# 03-ADC.net
KiCad netlist of a schematic drawn in Altium Designer
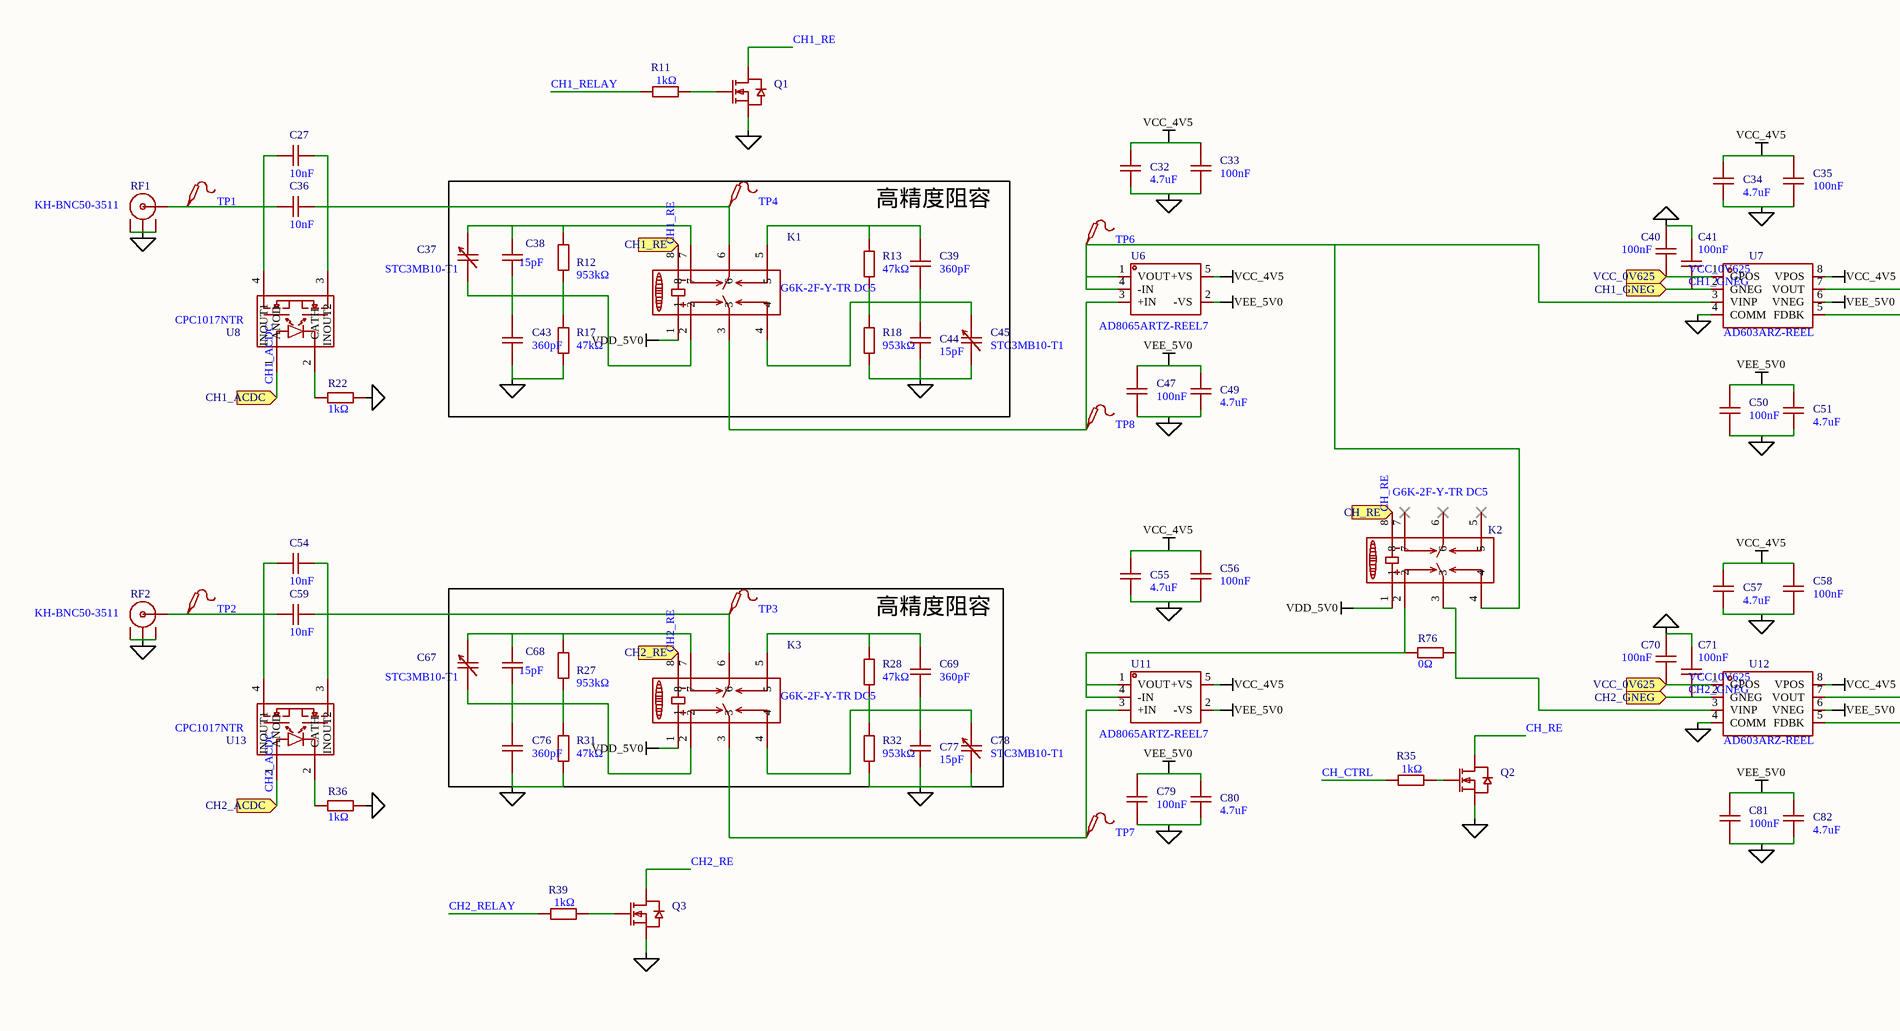
[diagram p0: 03-ADC.schdoc, left]
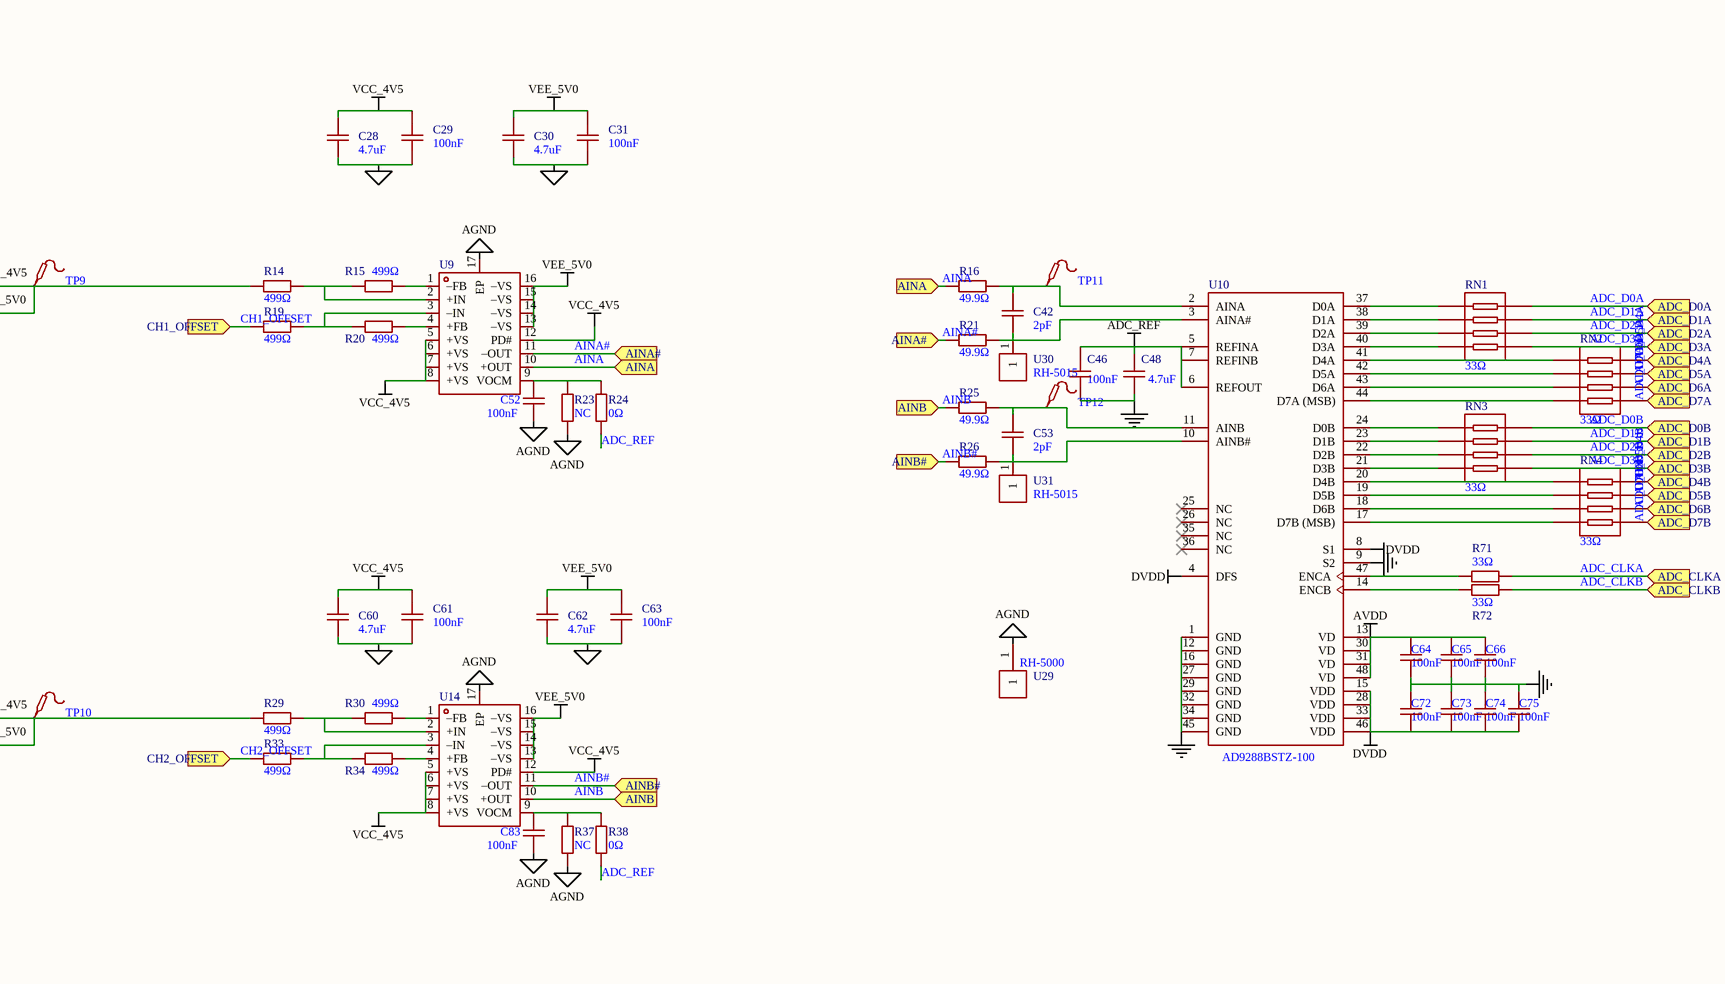
[diagram p1: 03-ADC.schdoc, right]

(export (version "E")
  (design (tool "Eeschema 10.0.6"))
  (components
    (comp (ref "C27")
      (value "10nF")
      (footprint "C0603")
      (fields
        (field (name "MANUFACTURER") "YAGEO(国巨)")
        (field (name "MANUFACTURER PART") "CC0603KRX7R9BB103")
        (field (name "TOLERANCE") "±10%")
      )
      (libsource (lib "altium-import") (part "root_0_CC0603KRX7R9BB103_"))
    )
    (comp (ref "C28")
      (value "4.7uF")
      (footprint "C0603")
      (fields
        (field (name "MANUFACTURER") "SAMSUNG(三星)")
        (field (name "MANUFACTURER PART") "CL10A475KO8NNNC")
        (field (name "TOLERANCE") "±10%")
      )
      (libsource (lib "altium-import") (part "root_1_CL10A475KO8NNNC_"))
    )
    (comp (ref "C29")
      (value "100nF")
      (footprint "C0603")
      (fields
        (field (name "MANUFACTURER") "HRE(芯声)")
        (field (name "MANUFACTURER PART") "CGA0603X7R104K500JT")
        (field (name "TOLERANCE") "±10%")
      )
      (libsource (lib "") (part "root_1_CGA0603X7R104K500JT__1"))
    )
    (comp (ref "C30")
      (value "4.7uF")
      (footprint "C0603")
      (fields
        (field (name "MANUFACTURER") "SAMSUNG(三星)")
        (field (name "MANUFACTURER PART") "CL10A475KO8NNNC")
        (field (name "TOLERANCE") "±10%")
      )
      (libsource (lib "altium-import") (part "root_1_CL10A475KO8NNNC_"))
    )
    (comp (ref "C31")
      (value "100nF")
      (footprint "C0603")
      (fields
        (field (name "MANUFACTURER") "HRE(芯声)")
        (field (name "MANUFACTURER PART") "CGA0603X7R104K500JT")
        (field (name "TOLERANCE") "±10%")
      )
      (libsource (lib "") (part "root_1_CGA0603X7R104K500JT__1"))
    )
    (comp (ref "C32")
      (value "4.7uF")
      (footprint "C0603")
      (fields
        (field (name "MANUFACTURER") "SAMSUNG(三星)")
        (field (name "MANUFACTURER PART") "CL10A475KO8NNNC")
        (field (name "TOLERANCE") "±10%")
      )
      (libsource (lib "altium-import") (part "root_1_CL10A475KO8NNNC_"))
    )
    (comp (ref "C33")
      (value "100nF")
      (footprint "C0603")
      (fields
        (field (name "MANUFACTURER") "HRE(芯声)")
        (field (name "MANUFACTURER PART") "CGA0603X7R104K500JT")
        (field (name "TOLERANCE") "±10%")
      )
      (libsource (lib "") (part "root_1_CGA0603X7R104K500JT__1"))
    )
    (comp (ref "C34")
      (value "4.7uF")
      (footprint "C0603")
      (fields
        (field (name "MANUFACTURER") "SAMSUNG(三星)")
        (field (name "MANUFACTURER PART") "CL10A475KO8NNNC")
        (field (name "TOLERANCE") "±10%")
      )
      (libsource (lib "altium-import") (part "root_1_CL10A475KO8NNNC_"))
    )
    (comp (ref "C35")
      (value "100nF")
      (footprint "C0603")
      (fields
        (field (name "MANUFACTURER") "HRE(芯声)")
        (field (name "MANUFACTURER PART") "CGA0603X7R104K500JT")
        (field (name "TOLERANCE") "±10%")
      )
      (libsource (lib "") (part "root_1_CGA0603X7R104K500JT__1"))
    )
    (comp (ref "C36")
      (value "10nF")
      (footprint "C0603")
      (fields
        (field (name "MANUFACTURER") "YAGEO(国巨)")
        (field (name "MANUFACTURER PART") "CC0603KRX7R9BB103")
        (field (name "TOLERANCE") "±10%")
      )
      (libsource (lib "altium-import") (part "root_0_CC0603KRX7R9BB103_"))
    )
    (comp (ref "C37")
      (value "STC3MB10-T1")
      (footprint "CAP-SMD_L4.5-W3.2_STC3MD20-T1")
      (fields (field (name "MANUFACTURER") "SEHWA(韩国世华)") (field (name "TOLERANCE") "0%~+50%"))
      (libsource (lib "altium-import") (part "root_1_STC3MB10-T1_"))
    )
    (comp (ref "C38")
      (value "15pF")
      (footprint "C0603")
      (fields
        (field (name "MANUFACTURER") "SAMSUNG(三星)")
        (field (name "MANUFACTURER PART") "CL10C150JB8NNNC")
        (field (name "TOLERANCE") "±5%")
      )
      (libsource (lib "altium-import") (part "root_1_CL10C150JB8NNNC_"))
    )
    (comp (ref "C39")
      (value "360pF")
      (footprint "C0603")
      (fields
        (field (name "MANUFACTURER") "YAGEO(国巨)")
        (field (name "MANUFACTURER PART") "CC0603JRNPO9BN361")
        (field (name "TOLERANCE") "±5%")
      )
      (libsource (lib "altium-import") (part "root_3_CC0603JRNPO9BN361_"))
    )
    (comp (ref "C40")
      (value "100nF")
      (footprint "C0603")
      (fields
        (field (name "MANUFACTURER") "HRE(芯声)")
        (field (name "MANUFACTURER PART") "CGA0603X7R104K500JT")
        (field (name "TOLERANCE") "±10%")
      )
      (libsource (lib "") (part "root_3_CGA0603X7R104K500JT__1"))
    )
    (comp (ref "C41")
      (value "100nF")
      (footprint "C0603")
      (fields
        (field (name "MANUFACTURER") "HRE(芯声)")
        (field (name "MANUFACTURER PART") "CGA0603X7R104K500JT")
        (field (name "TOLERANCE") "±10%")
      )
      (libsource (lib "") (part "root_1_CGA0603X7R104K500JT__1"))
    )
    (comp (ref "C42")
      (value "2pF")
      (footprint "C0603")
      (fields (field (name "MANUFACTURER") "FH(风华)") (field (name "MANUFACTURER PART") "0603CG2R0C500NT"))
      (libsource (lib "altium-import") (part "root_1_0603CG2R0C500NT_"))
    )
    (comp (ref "C43")
      (value "360pF")
      (footprint "C0603")
      (fields
        (field (name "MANUFACTURER") "YAGEO(国巨)")
        (field (name "MANUFACTURER PART") "CC0603JRNPO9BN361")
        (field (name "TOLERANCE") "±5%")
      )
      (libsource (lib "altium-import") (part "root_1_CC0603JRNPO9BN361_"))
    )
    (comp (ref "C44")
      (value "15pF")
      (footprint "C0603")
      (fields
        (field (name "MANUFACTURER") "SAMSUNG(三星)")
        (field (name "MANUFACTURER PART") "CL10C150JB8NNNC")
        (field (name "TOLERANCE") "±5%")
      )
      (libsource (lib "altium-import") (part "root_3_CL10C150JB8NNNC_"))
    )
    (comp (ref "C45")
      (value "STC3MB10-T1")
      (footprint "CAP-SMD_L4.5-W3.2_STC3MD20-T1")
      (fields (field (name "MANUFACTURER") "SEHWA(韩国世华)") (field (name "TOLERANCE") "0%~+50%"))
      (libsource (lib "altium-import") (part "root_1_STC3MB10-T1_"))
    )
    (comp (ref "C46")
      (value "100nF")
      (footprint "C0603")
      (fields
        (field (name "MANUFACTURER") "HRE(芯声)")
        (field (name "MANUFACTURER PART") "CGA0603X7R104K500JT")
        (field (name "TOLERANCE") "±10%")
      )
      (libsource (lib "") (part "root_1_CGA0603X7R104K500JT__1"))
    )
    (comp (ref "C47")
      (value "100nF")
      (footprint "C0603")
      (fields
        (field (name "MANUFACTURER") "HRE(芯声)")
        (field (name "MANUFACTURER PART") "CGA0603X7R104K500JT")
        (field (name "TOLERANCE") "±10%")
      )
      (libsource (lib "") (part "root_1_CGA0603X7R104K500JT__1"))
    )
    (comp (ref "C48")
      (value "4.7uF")
      (footprint "C0603")
      (fields
        (field (name "MANUFACTURER") "SAMSUNG(三星)")
        (field (name "MANUFACTURER PART") "CL10A475KO8NNNC")
        (field (name "TOLERANCE") "±10%")
      )
      (libsource (lib "altium-import") (part "root_1_CL10A475KO8NNNC_"))
    )
    (comp (ref "C49")
      (value "4.7uF")
      (footprint "C0603")
      (fields
        (field (name "MANUFACTURER") "SAMSUNG(三星)")
        (field (name "MANUFACTURER PART") "CL10A475KO8NNNC")
        (field (name "TOLERANCE") "±10%")
      )
      (libsource (lib "altium-import") (part "root_1_CL10A475KO8NNNC_"))
    )
    (comp (ref "C50")
      (value "100nF")
      (footprint "C0603")
      (fields
        (field (name "MANUFACTURER") "HRE(芯声)")
        (field (name "MANUFACTURER PART") "CGA0603X7R104K500JT")
        (field (name "TOLERANCE") "±10%")
      )
      (libsource (lib "") (part "root_1_CGA0603X7R104K500JT__1"))
    )
    (comp (ref "C51")
      (value "4.7uF")
      (footprint "C0603")
      (fields
        (field (name "MANUFACTURER") "SAMSUNG(三星)")
        (field (name "MANUFACTURER PART") "CL10A475KO8NNNC")
        (field (name "TOLERANCE") "±10%")
      )
      (libsource (lib "altium-import") (part "root_1_CL10A475KO8NNNC_"))
    )
    (comp (ref "C52")
      (value "100nF")
      (footprint "C0603")
      (fields
        (field (name "MANUFACTURER") "HRE(芯声)")
        (field (name "MANUFACTURER PART") "CGA0603X7R104K500JT")
        (field (name "ALTIUM_VALUE") "100nF")
        (field (name "TOLERANCE") "±10%")
      )
      (libsource (lib "altium-import") (part "root_1_CGA0603X7R104K500JT_"))
    )
    (comp (ref "C53")
      (value "2pF")
      (footprint "C0603")
      (fields (field (name "MANUFACTURER") "FH(风华)") (field (name "MANUFACTURER PART") "0603CG2R0C500NT"))
      (libsource (lib "altium-import") (part "root_1_0603CG2R0C500NT_"))
    )
    (comp (ref "C54")
      (value "10nF")
      (footprint "C0603")
      (fields
        (field (name "MANUFACTURER") "YAGEO(国巨)")
        (field (name "MANUFACTURER PART") "CC0603KRX7R9BB103")
        (field (name "TOLERANCE") "±10%")
      )
      (libsource (lib "altium-import") (part "root_0_CC0603KRX7R9BB103_"))
    )
    (comp (ref "C55")
      (value "4.7uF")
      (footprint "C0603")
      (fields
        (field (name "MANUFACTURER") "SAMSUNG(三星)")
        (field (name "MANUFACTURER PART") "CL10A475KO8NNNC")
        (field (name "TOLERANCE") "±10%")
      )
      (libsource (lib "altium-import") (part "root_1_CL10A475KO8NNNC_"))
    )
    (comp (ref "C56")
      (value "100nF")
      (footprint "C0603")
      (fields
        (field (name "MANUFACTURER") "HRE(芯声)")
        (field (name "MANUFACTURER PART") "CGA0603X7R104K500JT")
        (field (name "TOLERANCE") "±10%")
      )
      (libsource (lib "") (part "root_1_CGA0603X7R104K500JT__1"))
    )
    (comp (ref "C57")
      (value "4.7uF")
      (footprint "C0603")
      (fields
        (field (name "MANUFACTURER") "SAMSUNG(三星)")
        (field (name "MANUFACTURER PART") "CL10A475KO8NNNC")
        (field (name "TOLERANCE") "±10%")
      )
      (libsource (lib "altium-import") (part "root_1_CL10A475KO8NNNC_"))
    )
    (comp (ref "C58")
      (value "100nF")
      (footprint "C0603")
      (fields
        (field (name "MANUFACTURER") "HRE(芯声)")
        (field (name "MANUFACTURER PART") "CGA0603X7R104K500JT")
        (field (name "TOLERANCE") "±10%")
      )
      (libsource (lib "") (part "root_1_CGA0603X7R104K500JT__1"))
    )
    (comp (ref "C59")
      (value "10nF")
      (footprint "C0603")
      (fields
        (field (name "MANUFACTURER") "YAGEO(国巨)")
        (field (name "MANUFACTURER PART") "CC0603KRX7R9BB103")
        (field (name "TOLERANCE") "±10%")
      )
      (libsource (lib "altium-import") (part "root_0_CC0603KRX7R9BB103_"))
    )
    (comp (ref "C60")
      (value "4.7uF")
      (footprint "C0603")
      (fields
        (field (name "MANUFACTURER") "SAMSUNG(三星)")
        (field (name "MANUFACTURER PART") "CL10A475KO8NNNC")
        (field (name "TOLERANCE") "±10%")
      )
      (libsource (lib "altium-import") (part "root_1_CL10A475KO8NNNC_"))
    )
    (comp (ref "C61")
      (value "100nF")
      (footprint "C0603")
      (fields
        (field (name "MANUFACTURER") "HRE(芯声)")
        (field (name "MANUFACTURER PART") "CGA0603X7R104K500JT")
        (field (name "TOLERANCE") "±10%")
      )
      (libsource (lib "") (part "root_1_CGA0603X7R104K500JT__1"))
    )
    (comp (ref "C62")
      (value "4.7uF")
      (footprint "C0603")
      (fields
        (field (name "MANUFACTURER") "SAMSUNG(三星)")
        (field (name "MANUFACTURER PART") "CL10A475KO8NNNC")
        (field (name "TOLERANCE") "±10%")
      )
      (libsource (lib "altium-import") (part "root_1_CL10A475KO8NNNC_"))
    )
    (comp (ref "C63")
      (value "100nF")
      (footprint "C0603")
      (fields
        (field (name "MANUFACTURER") "HRE(芯声)")
        (field (name "MANUFACTURER PART") "CGA0603X7R104K500JT")
        (field (name "TOLERANCE") "±10%")
      )
      (libsource (lib "") (part "root_1_CGA0603X7R104K500JT__1"))
    )
    (comp (ref "C64")
      (value "100nF")
      (footprint "C0603")
      (fields
        (field (name "MANUFACTURER") "HRE(芯声)")
        (field (name "MANUFACTURER PART") "CGA0603X7R104K500JT")
        (field (name "ALTIUM_VALUE") "100nF")
        (field (name "TOLERANCE") "±10%")
      )
      (libsource (lib "altium-import") (part "root_3_CGA0603X7R104K500JT_"))
    )
    (comp (ref "C65")
      (value "100nF")
      (footprint "C0603")
      (fields
        (field (name "MANUFACTURER") "HRE(芯声)")
        (field (name "MANUFACTURER PART") "CGA0603X7R104K500JT")
        (field (name "ALTIUM_VALUE") "100nF")
        (field (name "TOLERANCE") "±10%")
      )
      (libsource (lib "altium-import") (part "root_3_CGA0603X7R104K500JT_"))
    )
    (comp (ref "C66")
      (value "100nF")
      (footprint "C0603")
      (fields
        (field (name "MANUFACTURER") "HRE(芯声)")
        (field (name "MANUFACTURER PART") "CGA0603X7R104K500JT")
        (field (name "ALTIUM_VALUE") "100nF")
        (field (name "TOLERANCE") "±10%")
      )
      (libsource (lib "altium-import") (part "root_3_CGA0603X7R104K500JT_"))
    )
    (comp (ref "C67")
      (value "STC3MB10-T1")
      (footprint "CAP-SMD_L4.5-W3.2_STC3MD20-T1")
      (fields (field (name "MANUFACTURER") "SEHWA(韩国世华)") (field (name "TOLERANCE") "0%~+50%"))
      (libsource (lib "altium-import") (part "root_1_STC3MB10-T1_"))
    )
    (comp (ref "C68")
      (value "15pF")
      (footprint "C0603")
      (fields
        (field (name "MANUFACTURER") "SAMSUNG(三星)")
        (field (name "MANUFACTURER PART") "CL10C150JB8NNNC")
        (field (name "TOLERANCE") "±5%")
      )
      (libsource (lib "altium-import") (part "root_1_CL10C150JB8NNNC_"))
    )
    (comp (ref "C69")
      (value "360pF")
      (footprint "C0603")
      (fields
        (field (name "MANUFACTURER") "YAGEO(国巨)")
        (field (name "MANUFACTURER PART") "CC0603JRNPO9BN361")
        (field (name "TOLERANCE") "±5%")
      )
      (libsource (lib "altium-import") (part "root_3_CC0603JRNPO9BN361_"))
    )
    (comp (ref "C70")
      (value "100nF")
      (footprint "C0603")
      (fields
        (field (name "MANUFACTURER") "HRE(芯声)")
        (field (name "MANUFACTURER PART") "CGA0603X7R104K500JT")
        (field (name "TOLERANCE") "±10%")
      )
      (libsource (lib "") (part "root_3_CGA0603X7R104K500JT__1"))
    )
    (comp (ref "C71")
      (value "100nF")
      (footprint "C0603")
      (fields
        (field (name "MANUFACTURER") "HRE(芯声)")
        (field (name "MANUFACTURER PART") "CGA0603X7R104K500JT")
        (field (name "TOLERANCE") "±10%")
      )
      (libsource (lib "") (part "root_1_CGA0603X7R104K500JT__1"))
    )
    (comp (ref "C72")
      (value "100nF")
      (footprint "C0603")
      (fields
        (field (name "MANUFACTURER") "HRE(芯声)")
        (field (name "MANUFACTURER PART") "CGA0603X7R104K500JT")
        (field (name "ALTIUM_VALUE") "100nF")
        (field (name "TOLERANCE") "±10%")
      )
      (libsource (lib "altium-import") (part "root_3_CGA0603X7R104K500JT_"))
    )
    (comp (ref "C73")
      (value "100nF")
      (footprint "C0603")
      (fields
        (field (name "MANUFACTURER") "HRE(芯声)")
        (field (name "MANUFACTURER PART") "CGA0603X7R104K500JT")
        (field (name "ALTIUM_VALUE") "100nF")
        (field (name "TOLERANCE") "±10%")
      )
      (libsource (lib "altium-import") (part "root_3_CGA0603X7R104K500JT_"))
    )
    (comp (ref "C74")
      (value "100nF")
      (footprint "C0603")
      (fields
        (field (name "MANUFACTURER") "HRE(芯声)")
        (field (name "MANUFACTURER PART") "CGA0603X7R104K500JT")
        (field (name "ALTIUM_VALUE") "100nF")
        (field (name "TOLERANCE") "±10%")
      )
      (libsource (lib "altium-import") (part "root_3_CGA0603X7R104K500JT_"))
    )
    (comp (ref "C75")
      (value "100nF")
      (footprint "C0603")
      (fields
        (field (name "MANUFACTURER") "HRE(芯声)")
        (field (name "MANUFACTURER PART") "CGA0603X7R104K500JT")
        (field (name "ALTIUM_VALUE") "100nF")
        (field (name "TOLERANCE") "±10%")
      )
      (libsource (lib "altium-import") (part "root_3_CGA0603X7R104K500JT_"))
    )
    (comp (ref "C76")
      (value "360pF")
      (footprint "C0603")
      (fields
        (field (name "MANUFACTURER") "YAGEO(国巨)")
        (field (name "MANUFACTURER PART") "CC0603JRNPO9BN361")
        (field (name "TOLERANCE") "±5%")
      )
      (libsource (lib "altium-import") (part "root_1_CC0603JRNPO9BN361_"))
    )
    (comp (ref "C77")
      (value "15pF")
      (footprint "C0603")
      (fields
        (field (name "MANUFACTURER") "SAMSUNG(三星)")
        (field (name "MANUFACTURER PART") "CL10C150JB8NNNC")
        (field (name "TOLERANCE") "±5%")
      )
      (libsource (lib "altium-import") (part "root_3_CL10C150JB8NNNC_"))
    )
    (comp (ref "C78")
      (value "STC3MB10-T1")
      (footprint "CAP-SMD_L4.5-W3.2_STC3MD20-T1")
      (fields (field (name "MANUFACTURER") "SEHWA(韩国世华)") (field (name "TOLERANCE") "0%~+50%"))
      (libsource (lib "altium-import") (part "root_1_STC3MB10-T1_"))
    )
    (comp (ref "C79")
      (value "100nF")
      (footprint "C0603")
      (fields
        (field (name "MANUFACTURER") "HRE(芯声)")
        (field (name "MANUFACTURER PART") "CGA0603X7R104K500JT")
        (field (name "TOLERANCE") "±10%")
      )
      (libsource (lib "") (part "root_1_CGA0603X7R104K500JT__1"))
    )
    (comp (ref "C80")
      (value "4.7uF")
      (footprint "C0603")
      (fields
        (field (name "MANUFACTURER") "SAMSUNG(三星)")
        (field (name "MANUFACTURER PART") "CL10A475KO8NNNC")
        (field (name "TOLERANCE") "±10%")
      )
      (libsource (lib "altium-import") (part "root_1_CL10A475KO8NNNC_"))
    )
    (comp (ref "C81")
      (value "100nF")
      (footprint "C0603")
      (fields
        (field (name "MANUFACTURER") "HRE(芯声)")
        (field (name "MANUFACTURER PART") "CGA0603X7R104K500JT")
        (field (name "TOLERANCE") "±10%")
      )
      (libsource (lib "") (part "root_1_CGA0603X7R104K500JT__1"))
    )
    (comp (ref "C82")
      (value "4.7uF")
      (footprint "C0603")
      (fields
        (field (name "MANUFACTURER") "SAMSUNG(三星)")
        (field (name "MANUFACTURER PART") "CL10A475KO8NNNC")
        (field (name "TOLERANCE") "±10%")
      )
      (libsource (lib "altium-import") (part "root_1_CL10A475KO8NNNC_"))
    )
    (comp (ref "C83")
      (value "100nF")
      (footprint "C0603")
      (fields
        (field (name "MANUFACTURER") "HRE(芯声)")
        (field (name "MANUFACTURER PART") "CGA0603X7R104K500JT")
        (field (name "ALTIUM_VALUE") "100nF")
        (field (name "TOLERANCE") "±10%")
      )
      (libsource (lib "altium-import") (part "root_1_CGA0603X7R104K500JT_"))
    )
    (comp (ref "K1")
      (value "G6K-2F-Y-TR DC5")
      (footprint "RELAY-SMD_G6K-2F-X-XX")
      (fields (field (name "MANUFACTURER") "OMRON(欧姆龙)"))
      (libsource (lib "altium-import") (part "root_0_G6K-2F-Y-TR DC5_"))
    )
    (comp (ref "K2")
      (value "G6K-2F-Y-TR DC5")
      (footprint "RELAY-SMD_G6K-2F-X-XX")
      (fields (field (name "MANUFACTURER") "OMRON(欧姆龙)"))
      (libsource (lib "altium-import") (part "root_0_G6K-2F-Y-TR DC5_"))
    )
    (comp (ref "K3")
      (value "G6K-2F-Y-TR DC5")
      (footprint "RELAY-SMD_G6K-2F-X-XX")
      (fields (field (name "MANUFACTURER") "OMRON(欧姆龙)"))
      (libsource (lib "altium-import") (part "root_0_G6K-2F-Y-TR DC5_"))
    )
    (comp (ref "Q1")
      (value "~")
      (footprint "sot-23-3_l2.9-w1.3-p1.90-ls2.4-br")
      (fields (field (name "MANUFACTURER") "HUASHUO(华朔)") (field (name "MANUFACTURER PART") "BSS138"))
      (libsource (lib "altium-import") (part "root_0_BSS138_C518792_"))
    )
    (comp (ref "Q2")
      (value "~")
      (footprint "sot-23-3_l2.9-w1.3-p1.90-ls2.4-br")
      (fields (field (name "MANUFACTURER") "HUASHUO(华朔)") (field (name "MANUFACTURER PART") "BSS138"))
      (libsource (lib "altium-import") (part "root_0_BSS138_C518792_"))
    )
    (comp (ref "Q3")
      (value "~")
      (footprint "sot-23-3_l2.9-w1.3-p1.90-ls2.4-br")
      (fields (field (name "MANUFACTURER") "HUASHUO(华朔)") (field (name "MANUFACTURER PART") "BSS138"))
      (libsource (lib "altium-import") (part "root_0_BSS138_C518792_"))
    )
    (comp (ref "R11")
      (value "1kΩ")
      (footprint "R0603")
      (fields
        (field (name "MANUFACTURER") "UNI-ROYAL(厚声)")
        (field (name "MANUFACTURER PART") "0603WAF1001T5E")
        (field (name "ALTIUM_VALUE") "1kΩ")
        (field (name "TOLERANCE") "±1%")
      )
      (libsource (lib "altium-import") (part "root_2_0603WAF1001T5E_"))
    )
    (comp (ref "R12")
      (value "953kΩ")
      (footprint "R0603")
      (fields
        (field (name "MANUFACTURER") "UNI-ROYAL(厚声)")
        (field (name "MANUFACTURER PART") "0603WAF9533T5E")
        (field (name "TOLERANCE") "±1%")
      )
      (libsource (lib "altium-import") (part "root_1_0603WAF9533T5E_"))
    )
    (comp (ref "R13")
      (value "47kΩ")
      (footprint "R0603")
      (fields
        (field (name "MANUFACTURER") "UNI-ROYAL(厚声)")
        (field (name "MANUFACTURER PART") "0603WAF4702T5E")
        (field (name "TOLERANCE") "±1%")
      )
      (libsource (lib "altium-import") (part "root_3_0603WAF4702T5E_"))
    )
    (comp (ref "R14")
      (value "499Ω")
      (footprint "R0603")
      (fields
        (field (name "MANUFACTURER") "UNI-ROYAL(厚声)")
        (field (name "MANUFACTURER PART") "0603WAF4990T5E")
        (field (name "TOLERANCE") "±1%")
      )
      (libsource (lib "altium-import") (part "root_0_0603WAF4990T5E_"))
    )
    (comp (ref "R15")
      (value "499Ω")
      (footprint "R0603")
      (fields
        (field (name "MANUFACTURER") "UNI-ROYAL(厚声)")
        (field (name "MANUFACTURER PART") "0603WAF4990T5E")
        (field (name "TOLERANCE") "±1%")
      )
      (libsource (lib "altium-import") (part "root_0_0603WAF4990T5E_"))
    )
    (comp (ref "R16")
      (value "49.9Ω")
      (footprint "R0603")
      (fields
        (field (name "MANUFACTURER") "UNI-ROYAL(厚声)")
        (field (name "MANUFACTURER PART") "0603WAF499JT5E")
        (field (name "TOLERANCE") "±1%")
      )
      (libsource (lib "altium-import") (part "root_0_0603WAF499JT5E_"))
    )
    (comp (ref "R17")
      (value "47kΩ")
      (footprint "R0603")
      (fields
        (field (name "MANUFACTURER") "UNI-ROYAL(厚声)")
        (field (name "MANUFACTURER PART") "0603WAF4702T5E")
        (field (name "TOLERANCE") "±1%")
      )
      (libsource (lib "altium-import") (part "root_1_0603WAF4702T5E_"))
    )
    (comp (ref "R18")
      (value "953kΩ")
      (footprint "R0603")
      (fields
        (field (name "MANUFACTURER") "UNI-ROYAL(厚声)")
        (field (name "MANUFACTURER PART") "0603WAF9533T5E")
        (field (name "TOLERANCE") "±1%")
      )
      (libsource (lib "altium-import") (part "root_3_0603WAF9533T5E_"))
    )
    (comp (ref "R19")
      (value "499Ω")
      (footprint "R0603")
      (fields
        (field (name "MANUFACTURER") "UNI-ROYAL(厚声)")
        (field (name "MANUFACTURER PART") "0603WAF4990T5E")
        (field (name "TOLERANCE") "±1%")
      )
      (libsource (lib "altium-import") (part "root_0_0603WAF4990T5E_"))
    )
    (comp (ref "R20")
      (value "499Ω")
      (footprint "R0603")
      (fields
        (field (name "MANUFACTURER") "UNI-ROYAL(厚声)")
        (field (name "MANUFACTURER PART") "0603WAF4990T5E")
        (field (name "TOLERANCE") "±1%")
      )
      (libsource (lib "altium-import") (part "root_0_0603WAF4990T5E_"))
    )
    (comp (ref "R21")
      (value "49.9Ω")
      (footprint "R0603")
      (fields
        (field (name "MANUFACTURER") "UNI-ROYAL(厚声)")
        (field (name "MANUFACTURER PART") "0603WAF499JT5E")
        (field (name "TOLERANCE") "±1%")
      )
      (libsource (lib "altium-import") (part "root_0_0603WAF499JT5E_"))
    )
    (comp (ref "R22")
      (value "1kΩ")
      (footprint "R0603")
      (fields
        (field (name "MANUFACTURER") "UNI-ROYAL(厚声)")
        (field (name "MANUFACTURER PART") "0603WAF1001T5E")
        (field (name "TOLERANCE") "±1%")
      )
      (libsource (lib "altium-import") (part "root_2_0603WAF1001T5E_"))
    )
    (comp (ref "R23")
      (value "NC")
      (footprint "R0603")
      (fields
        (field (name "MANUFACTURER") "UNI-ROYAL(厚声)")
        (field (name "MANUFACTURER PART") "0603WAF0000T5E")
        (field (name "TOLERANCE") "±1%")
      )
      (libsource (lib "altium-import") (part "root_1_0603WAF0000T5E_"))
    )
    (comp (ref "R24")
      (value "0Ω")
      (footprint "R0603")
      (fields
        (field (name "MANUFACTURER") "UNI-ROYAL(厚声)")
        (field (name "MANUFACTURER PART") "0603WAF0000T5E")
        (field (name "TOLERANCE") "±1%")
      )
      (libsource (lib "altium-import") (part "root_1_0603WAF0000T5E_"))
    )
    (comp (ref "R25")
      (value "49.9Ω")
      (footprint "R0603")
      (fields
        (field (name "MANUFACTURER") "UNI-ROYAL(厚声)")
        (field (name "MANUFACTURER PART") "0603WAF499JT5E")
        (field (name "TOLERANCE") "±1%")
      )
      (libsource (lib "altium-import") (part "root_0_0603WAF499JT5E_"))
    )
    (comp (ref "R26")
      (value "49.9Ω")
      (footprint "R0603")
      (fields
        (field (name "MANUFACTURER") "UNI-ROYAL(厚声)")
        (field (name "MANUFACTURER PART") "0603WAF499JT5E")
        (field (name "TOLERANCE") "±1%")
      )
      (libsource (lib "altium-import") (part "root_0_0603WAF499JT5E_"))
    )
    (comp (ref "R27")
      (value "953kΩ")
      (footprint "R0603")
      (fields
        (field (name "MANUFACTURER") "UNI-ROYAL(厚声)")
        (field (name "MANUFACTURER PART") "0603WAF9533T5E")
        (field (name "TOLERANCE") "±1%")
      )
      (libsource (lib "altium-import") (part "root_1_0603WAF9533T5E_"))
    )
    (comp (ref "R28")
      (value "47kΩ")
      (footprint "R0603")
      (fields
        (field (name "MANUFACTURER") "UNI-ROYAL(厚声)")
        (field (name "MANUFACTURER PART") "0603WAF4702T5E")
        (field (name "TOLERANCE") "±1%")
      )
      (libsource (lib "altium-import") (part "root_3_0603WAF4702T5E_"))
    )
    (comp (ref "R29")
      (value "499Ω")
      (footprint "R0603")
      (fields
        (field (name "MANUFACTURER") "UNI-ROYAL(厚声)")
        (field (name "MANUFACTURER PART") "0603WAF4990T5E")
        (field (name "TOLERANCE") "±1%")
      )
      (libsource (lib "altium-import") (part "root_0_0603WAF4990T5E_"))
    )
    (comp (ref "R30")
      (value "499Ω")
      (footprint "R0603")
      (fields
        (field (name "MANUFACTURER") "UNI-ROYAL(厚声)")
        (field (name "MANUFACTURER PART") "0603WAF4990T5E")
        (field (name "TOLERANCE") "±1%")
      )
      (libsource (lib "altium-import") (part "root_0_0603WAF4990T5E_"))
    )
    (comp (ref "R31")
      (value "47kΩ")
      (footprint "R0603")
      (fields
        (field (name "MANUFACTURER") "UNI-ROYAL(厚声)")
        (field (name "MANUFACTURER PART") "0603WAF4702T5E")
        (field (name "TOLERANCE") "±1%")
      )
      (libsource (lib "altium-import") (part "root_1_0603WAF4702T5E_"))
    )
    (comp (ref "R32")
      (value "953kΩ")
      (footprint "R0603")
      (fields
        (field (name "MANUFACTURER") "UNI-ROYAL(厚声)")
        (field (name "MANUFACTURER PART") "0603WAF9533T5E")
        (field (name "TOLERANCE") "±1%")
      )
      (libsource (lib "altium-import") (part "root_3_0603WAF9533T5E_"))
    )
    (comp (ref "R33")
      (value "499Ω")
      (footprint "R0603")
      (fields
        (field (name "MANUFACTURER") "UNI-ROYAL(厚声)")
        (field (name "MANUFACTURER PART") "0603WAF4990T5E")
        (field (name "TOLERANCE") "±1%")
      )
      (libsource (lib "altium-import") (part "root_0_0603WAF4990T5E_"))
    )
    (comp (ref "R34")
      (value "499Ω")
      (footprint "R0603")
      (fields
        (field (name "MANUFACTURER") "UNI-ROYAL(厚声)")
        (field (name "MANUFACTURER PART") "0603WAF4990T5E")
        (field (name "TOLERANCE") "±1%")
      )
      (libsource (lib "altium-import") (part "root_0_0603WAF4990T5E_"))
    )
    (comp (ref "R35")
      (value "1kΩ")
      (footprint "R0603")
      (fields
        (field (name "MANUFACTURER") "UNI-ROYAL(厚声)")
        (field (name "MANUFACTURER PART") "0603WAF1001T5E")
        (field (name "ALTIUM_VALUE") "1kΩ")
        (field (name "TOLERANCE") "±1%")
      )
      (libsource (lib "altium-import") (part "root_2_0603WAF1001T5E_"))
    )
    (comp (ref "R36")
      (value "1kΩ")
      (footprint "R0603")
      (fields
        (field (name "MANUFACTURER") "UNI-ROYAL(厚声)")
        (field (name "MANUFACTURER PART") "0603WAF1001T5E")
        (field (name "TOLERANCE") "±1%")
      )
      (libsource (lib "altium-import") (part "root_2_0603WAF1001T5E_"))
    )
    (comp (ref "R37")
      (value "NC")
      (footprint "R0603")
      (fields
        (field (name "MANUFACTURER") "UNI-ROYAL(厚声)")
        (field (name "MANUFACTURER PART") "0603WAF0000T5E")
        (field (name "TOLERANCE") "±1%")
      )
      (libsource (lib "altium-import") (part "root_1_0603WAF0000T5E_"))
    )
    (comp (ref "R38")
      (value "0Ω")
      (footprint "R0603")
      (fields
        (field (name "MANUFACTURER") "UNI-ROYAL(厚声)")
        (field (name "MANUFACTURER PART") "0603WAF0000T5E")
        (field (name "TOLERANCE") "±1%")
      )
      (libsource (lib "altium-import") (part "root_1_0603WAF0000T5E_"))
    )
    (comp (ref "R39")
      (value "1kΩ")
      (footprint "R0603")
      (fields
        (field (name "MANUFACTURER") "UNI-ROYAL(厚声)")
        (field (name "MANUFACTURER PART") "0603WAF1001T5E")
        (field (name "ALTIUM_VALUE") "1kΩ")
        (field (name "TOLERANCE") "±1%")
      )
      (libsource (lib "altium-import") (part "root_2_0603WAF1001T5E_"))
    )
    (comp (ref "R71")
      (value "33Ω")
      (footprint "R0603")
      (fields
        (field (name "MANUFACTURER") "UNI-ROYAL(厚声)")
        (field (name "MANUFACTURER PART") "0603WAF330JT5E")
        (field (name "TOLERANCE") "±1%")
      )
      (libsource (lib "altium-import") (part "root_0_0603WAF330JT5E_"))
    )
    (comp (ref "R72")
      (value "33Ω")
      (footprint "R0603")
      (fields
        (field (name "MANUFACTURER") "UNI-ROYAL(厚声)")
        (field (name "MANUFACTURER PART") "0603WAF330JT5E")
        (field (name "TOLERANCE") "±1%")
      )
      (libsource (lib "altium-import") (part "root_0_0603WAF330JT5E_"))
    )
    (comp (ref "R76")
      (value "0Ω")
      (footprint "R0603")
      (fields
        (field (name "MANUFACTURER") "UNI-ROYAL(厚声)")
        (field (name "MANUFACTURER PART") "0603WAF0000T5E")
        (field (name "TOLERANCE") "±1%")
      )
      (libsource (lib "altium-import") (part "root_0_0603WAF0000T5E_"))
    )
    (comp (ref "RF1")
      (value "KH-BNC50-3511")
      (footprint "ANT-TH_KH-BNC50-3511")
      (fields (field (name "MANUFACTURER") "kinghelm(金航标)"))
      (libsource (lib "altium-import") (part "root_0_KH-BNC50-3511_"))
    )
    (comp (ref "RF2")
      (value "KH-BNC50-3511")
      (footprint "ANT-TH_KH-BNC50-3511")
      (fields (field (name "MANUFACTURER") "kinghelm(金航标)"))
      (libsource (lib "altium-import") (part "root_0_KH-BNC50-3511_"))
    )
    (comp (ref "RN1")
      (value "33Ω")
      (footprint "RES-ARRAY-SMD_0603-8P-L3.2-W1.6-BL")
      (fields
        (field (name "MANUFACTURER") "UNI-ROYAL(厚声)")
        (field (name "MANUFACTURER PART") "4D03WGJ0330T5E")
        (field (name "TOLERANCE") "±5%")
      )
      (libsource (lib "altium-import") (part "root_0_4D03WGJ0330T5E_"))
    )
    (comp (ref "RN2")
      (value "33Ω")
      (footprint "RES-ARRAY-SMD_0603-8P-L3.2-W1.6-BL")
      (fields
        (field (name "MANUFACTURER") "UNI-ROYAL(厚声)")
        (field (name "MANUFACTURER PART") "4D03WGJ0330T5E")
        (field (name "TOLERANCE") "±5%")
      )
      (libsource (lib "altium-import") (part "root_0_4D03WGJ0330T5E_"))
    )
    (comp (ref "RN3")
      (value "33Ω")
      (footprint "RES-ARRAY-SMD_0603-8P-L3.2-W1.6-BL")
      (fields
        (field (name "MANUFACTURER") "UNI-ROYAL(厚声)")
        (field (name "MANUFACTURER PART") "4D03WGJ0330T5E")
        (field (name "TOLERANCE") "±5%")
      )
      (libsource (lib "altium-import") (part "root_0_4D03WGJ0330T5E_"))
    )
    (comp (ref "RN4")
      (value "33Ω")
      (footprint "RES-ARRAY-SMD_0603-8P-L3.2-W1.6-BL")
      (fields
        (field (name "MANUFACTURER") "UNI-ROYAL(厚声)")
        (field (name "MANUFACTURER PART") "4D03WGJ0330T5E")
        (field (name "TOLERANCE") "±5%")
      )
      (libsource (lib "altium-import") (part "root_0_4D03WGJ0330T5E_"))
    )
    (comp (ref "TP1")
      (value "~")
      (footprint "Test-Point-0.5mm")
      (libsource (lib "altium-import") (part "root_0_Test-Point_"))
    )
    (comp (ref "TP2")
      (value "~")
      (footprint "Test-Point-0.5mm")
      (libsource (lib "altium-import") (part "root_0_Test-Point_"))
    )
    (comp (ref "TP3")
      (value "~")
      (footprint "Test-Point-0.5mm")
      (libsource (lib "altium-import") (part "root_0_Test-Point_"))
    )
    (comp (ref "TP4")
      (value "~")
      (footprint "Test-Point-0.5mm")
      (libsource (lib "altium-import") (part "root_0_Test-Point_"))
    )
    (comp (ref "TP6")
      (value "~")
      (footprint "Test-Point-0.5mm")
      (libsource (lib "altium-import") (part "root_0_Test-Point_"))
    )
    (comp (ref "TP7")
      (value "~")
      (footprint "Test-Point-0.5mm")
      (libsource (lib "altium-import") (part "root_0_Test-Point_"))
    )
    (comp (ref "TP8")
      (value "~")
      (footprint "Test-Point-0.5mm")
      (libsource (lib "altium-import") (part "root_0_Test-Point_"))
    )
    (comp (ref "TP9")
      (value "~")
      (footprint "Test-Point-0.5mm")
      (libsource (lib "altium-import") (part "root_0_Test-Point_"))
    )
    (comp (ref "TP10")
      (value "~")
      (footprint "Test-Point-0.5mm")
      (libsource (lib "altium-import") (part "root_0_Test-Point_"))
    )
    (comp (ref "TP11")
      (value "~")
      (footprint "Test-Point-0.5mm")
      (libsource (lib "altium-import") (part "root_0_Test-Point_"))
    )
    (comp (ref "TP12")
      (value "~")
      (footprint "Test-Point-0.5mm")
      (libsource (lib "altium-import") (part "root_0_Test-Point_"))
    )
    (comp (ref "U6")
      (value "AD8065ARTZ-REEL7")
      (footprint "SOT-23-5_L3.0-W1.7-P0.95-LS2.8-BL")
      (fields (field (name "MANUFACTURER") "ADI(亚德诺)"))
      (libsource (lib "altium-import") (part "root_0_AD8065ARTZ-REEL7_"))
    )
    (comp (ref "U7")
      (value "AD603ARZ-REEL")
      (footprint "SOIC-8_L4.9-W3.9-P1.27-LS6.0-BL")
      (fields (field (name "MANUFACTURER") "ADI(亚德诺)"))
      (libsource (lib "altium-import") (part "root_0_AD603ARZ-REEL_"))
    )
    (comp (ref "U8")
      (value "CPC1017NTR")
      (footprint "SOP-4_L4.1-W3.8-P2.54-LS6.1-BL")
      (fields (field (name "MANUFACTURER") "Littelfuse/IXYS"))
      (libsource (lib "altium-import") (part "root_1_CPC1017NTR_"))
    )
    (comp (ref "U9")
      (value "ADA4932-1YCPZ-R7")
      (footprint "LFCSP-16_L3.0-W3.0-P0.50-TL-EP")
      (fields (field (name "MANUFACTURER") "ADI(亚德诺)"))
      (libsource (lib "altium-import") (part "root_0_ADA4932-1YCPZ-R7_"))
    )
    (comp (ref "U10")
      (value "AD9288BSTZ-100")
      (footprint "LQFP-48_L7.0-W7.0-P0.50-LS9.0-BL")
      (fields (field (name "MANUFACTURER") "ADI(亚德诺)"))
      (libsource (lib "altium-import") (part "root_0_AD9288BSTZ-100_"))
    )
    (comp (ref "U11")
      (value "AD8065ARTZ-REEL7")
      (footprint "SOT-23-5_L3.0-W1.7-P0.95-LS2.8-BL")
      (fields (field (name "MANUFACTURER") "ADI(亚德诺)"))
      (libsource (lib "altium-import") (part "root_0_AD8065ARTZ-REEL7_"))
    )
    (comp (ref "U12")
      (value "AD603ARZ-REEL")
      (footprint "SOIC-8_L4.9-W3.9-P1.27-LS6.0-BL")
      (fields (field (name "MANUFACTURER") "ADI(亚德诺)"))
      (libsource (lib "altium-import") (part "root_0_AD603ARZ-REEL_"))
    )
    (comp (ref "U13")
      (value "CPC1017NTR")
      (footprint "SOP-4_L4.1-W3.8-P2.54-LS6.1-BL")
      (fields (field (name "MANUFACTURER") "Littelfuse/IXYS"))
      (libsource (lib "altium-import") (part "root_1_CPC1017NTR_"))
    )
    (comp (ref "U14")
      (value "ADA4932-1YCPZ-R7")
      (footprint "LFCSP-16_L3.0-W3.0-P0.50-TL-EP")
      (fields (field (name "MANUFACTURER") "ADI(亚德诺)"))
      (libsource (lib "altium-import") (part "root_0_ADA4932-1YCPZ-R7_"))
    )
    (comp (ref "U29")
      (value "RH-5000")
      (footprint "TEST-TH_BD2.54-P1.4_RED")
      (fields (field (name "MANUFACTURER") "荣和"))
      (libsource (lib "altium-import") (part "root_1_RH-5000_"))
    )
    (comp (ref "U30")
      (value "RH-5015")
      (footprint "SMD_RH-5015")
      (fields (field (name "MANUFACTURER") "荣和"))
      (libsource (lib "altium-import") (part "root_3_RH-5015_"))
    )
    (comp (ref "U31")
      (value "RH-5015")
      (footprint "SMD_RH-5015")
      (fields (field (name "MANUFACTURER") "荣和"))
      (libsource (lib "altium-import") (part "root_3_RH-5015_"))
    )
  )
  (nets
    (net (code "1") (name "/ADC_CLKA") (class "Default")
      (node (ref "R71") (pin "2") (pinfunction "2_2") (pintype "passive"))
    )
    (net (code "2") (name "/ADC_CLKB") (class "Default")
      (node (ref "R72") (pin "2") (pinfunction "2_2") (pintype "passive"))
    )
    (net (code "3") (name "/ADC_D0A") (class "Default")
      (node (ref "RN1") (pin "8") (pinfunction "8_8") (pintype "passive"))
    )
    (net (code "4") (name "/ADC_D0B") (class "Default")
      (node (ref "RN3") (pin "8") (pinfunction "8_8") (pintype "passive"))
    )
    (net (code "5") (name "/ADC_D1A") (class "Default")
      (node (ref "RN1") (pin "7") (pinfunction "7_7") (pintype "passive"))
    )
    (net (code "6") (name "/ADC_D1B") (class "Default")
      (node (ref "RN3") (pin "7") (pinfunction "7_7") (pintype "passive"))
    )
    (net (code "7") (name "/ADC_D2A") (class "Default")
      (node (ref "RN1") (pin "6") (pinfunction "6_6") (pintype "passive"))
    )
    (net (code "8") (name "/ADC_D2B") (class "Default")
      (node (ref "RN3") (pin "6") (pinfunction "6_6") (pintype "passive"))
    )
    (net (code "9") (name "/ADC_D3A") (class "Default")
      (node (ref "RN1") (pin "5") (pinfunction "5_5") (pintype "passive"))
    )
    (net (code "10") (name "/ADC_D3B") (class "Default")
      (node (ref "RN3") (pin "5") (pinfunction "5_5") (pintype "passive"))
    )
    (net (code "11") (name "/ADC_D4A") (class "Default")
      (node (ref "RN2") (pin "8") (pinfunction "8_8") (pintype "passive"))
    )
    (net (code "12") (name "/ADC_D4B") (class "Default")
      (node (ref "RN4") (pin "8") (pinfunction "8_8") (pintype "passive"))
    )
    (net (code "13") (name "/ADC_D5A") (class "Default")
      (node (ref "RN2") (pin "7") (pinfunction "7_7") (pintype "passive"))
    )
    (net (code "14") (name "/ADC_D5B") (class "Default")
      (node (ref "RN4") (pin "7") (pinfunction "7_7") (pintype "passive"))
    )
    (net (code "15") (name "/ADC_D6A") (class "Default")
      (node (ref "RN2") (pin "6") (pinfunction "6_6") (pintype "passive"))
    )
    (net (code "16") (name "/ADC_D6B") (class "Default")
      (node (ref "RN4") (pin "6") (pinfunction "6_6") (pintype "passive"))
    )
    (net (code "17") (name "/ADC_D7A") (class "Default")
      (node (ref "RN2") (pin "5") (pinfunction "5_5") (pintype "passive"))
    )
    (net (code "18") (name "/ADC_D7B") (class "Default")
      (node (ref "RN4") (pin "5") (pinfunction "5_5") (pintype "passive"))
    )
    (net (code "19") (name "/AINA") (class "Default")
      (node (ref "R16") (pin "1") (pinfunction "1_1") (pintype "passive"))
      (node (ref "U9") (pin "10") (pinfunction "+OUT_10") (pintype "passive"))
    )
    (net (code "20") (name "/AINA#") (class "Default")
      (node (ref "R21") (pin "1") (pinfunction "1_1") (pintype "passive"))
      (node (ref "U9") (pin "11") (pinfunction "–OUT_11") (pintype "passive"))
    )
    (net (code "21") (name "/AINB") (class "Default")
      (node (ref "R25") (pin "1") (pinfunction "1_1") (pintype "passive"))
      (node (ref "U14") (pin "10") (pinfunction "+OUT_10") (pintype "passive"))
    )
    (net (code "22") (name "/AINB#") (class "Default")
      (node (ref "R26") (pin "1") (pinfunction "1_1") (pintype "passive"))
      (node (ref "U14") (pin "11") (pinfunction "–OUT_11") (pintype "passive"))
    )
    (net (code "23") (name "/CH1_ACDC") (class "Default")
      (node (ref "U8") (pin "1") (pinfunction "ANOD_1") (pintype "passive"))
    )
    (net (code "24") (name "/CH1_GNEG") (class "Default")
      (node (ref "C41") (pin "1") (pinfunction "1_1") (pintype "passive"))
      (node (ref "U7") (pin "2") (pinfunction "GNEG_2") (pintype "passive"))
    )
    (net (code "25") (name "/CH1_OFFSET") (class "Default")
      (node (ref "R19") (pin "1") (pinfunction "1_1") (pintype "passive"))
    )
    (net (code "26") (name "/CH1_RE") (class "Default")
      (node (ref "K1") (pin "8") (pinfunction "8_8") (pintype "passive"))
      (node (ref "Q1") (pin "3") (pinfunction "D_3") (pintype "passive"))
    )
    (net (code "27") (name "/CH1_RELAY") (class "Default")
      (node (ref "R11") (pin "2") (pinfunction "2_2") (pintype "passive"))
    )
    (net (code "28") (name "/CH2_ACDC") (class "Default")
      (node (ref "U13") (pin "1") (pinfunction "ANOD_1") (pintype "passive"))
    )
    (net (code "29") (name "/CH2_GNEG") (class "Default")
      (node (ref "C71") (pin "1") (pinfunction "1_1") (pintype "passive"))
      (node (ref "U12") (pin "2") (pinfunction "GNEG_2") (pintype "passive"))
    )
    (net (code "30") (name "/CH2_OFFSET") (class "Default")
      (node (ref "R33") (pin "1") (pinfunction "1_1") (pintype "passive"))
    )
    (net (code "31") (name "/CH2_RE") (class "Default")
      (node (ref "K3") (pin "8") (pinfunction "8_8") (pintype "passive"))
      (node (ref "Q3") (pin "3") (pinfunction "D_3") (pintype "passive"))
    )
    (net (code "32") (name "/CH2_RELAY") (class "Default")
      (node (ref "R39") (pin "2") (pinfunction "2_2") (pintype "passive"))
    )
    (net (code "33") (name "/CH_CTRL") (class "Default")
      (node (ref "R35") (pin "2") (pinfunction "2_2") (pintype "passive"))
    )
    (net (code "34") (name "/CH_RE") (class "Default")
      (node (ref "K2") (pin "8") (pinfunction "8_8") (pintype "passive"))
      (node (ref "Q2") (pin "3") (pinfunction "D_3") (pintype "passive"))
    )
    (net (code "35") (name "/VCC_0V625") (class "Default")
      (node (ref "C40") (pin "2") (pinfunction "2_2") (pintype "passive"))
      (node (ref "C70") (pin "2") (pinfunction "2_2") (pintype "passive"))
      (node (ref "U12") (pin "1") (pinfunction "GPOS_1") (pintype "passive"))
      (node (ref "U7") (pin "1") (pinfunction "GPOS_1") (pintype "passive"))
    )
    (net (code "36") (name "ADC_REF") (class "Default")
      (node (ref "C46") (pin "2") (pinfunction "2_2") (pintype "passive"))
      (node (ref "C48") (pin "2") (pinfunction "2_2") (pintype "passive"))
      (node (ref "R24") (pin "1") (pinfunction "1_1") (pintype "passive"))
      (node (ref "R38") (pin "1") (pinfunction "1_1") (pintype "passive"))
      (node (ref "U10") (pin "5") (pinfunction "REFINA_5") (pintype "passive"))
      (node (ref "U10") (pin "6") (pinfunction "REFOUT_6") (pintype "passive"))
      (node (ref "U10") (pin "7") (pinfunction "REFINB_7") (pintype "passive"))
    )
    (net (code "37") (name "AGND") (class "Default")
      (node (ref "C28") (pin "1") (pinfunction "1_1") (pintype "passive"))
      (node (ref "C29") (pin "1") (pinfunction "1_1") (pintype "passive"))
      (node (ref "C30") (pin "1") (pinfunction "1_1") (pintype "passive"))
      (node (ref "C31") (pin "1") (pinfunction "1_1") (pintype "passive"))
      (node (ref "C32") (pin "1") (pinfunction "1_1") (pintype "passive"))
      (node (ref "C33") (pin "1") (pinfunction "1_1") (pintype "passive"))
      (node (ref "C34") (pin "1") (pinfunction "1_1") (pintype "passive"))
      (node (ref "C35") (pin "1") (pinfunction "1_1") (pintype "passive"))
      (node (ref "C40") (pin "1") (pinfunction "1_1") (pintype "passive"))
      (node (ref "C41") (pin "2") (pinfunction "2_2") (pintype "passive"))
      (node (ref "C43") (pin "1") (pinfunction "1_1") (pintype "passive"))
      (node (ref "C44") (pin "2") (pinfunction "2_2") (pintype "passive"))
      (node (ref "C45") (pin "1") (pinfunction "1_1") (pintype "passive"))
      (node (ref "C47") (pin "1") (pinfunction "1_1") (pintype "passive"))
      (node (ref "C49") (pin "1") (pinfunction "1_1") (pintype "passive"))
      (node (ref "C50") (pin "1") (pinfunction "1_1") (pintype "passive"))
      (node (ref "C51") (pin "1") (pinfunction "1_1") (pintype "passive"))
      (node (ref "C52") (pin "1") (pinfunction "1_1") (pintype "passive"))
      (node (ref "C55") (pin "1") (pinfunction "1_1") (pintype "passive"))
      (node (ref "C56") (pin "1") (pinfunction "1_1") (pintype "passive"))
      (node (ref "C57") (pin "1") (pinfunction "1_1") (pintype "passive"))
      (node (ref "C58") (pin "1") (pinfunction "1_1") (pintype "passive"))
      (node (ref "C60") (pin "1") (pinfunction "1_1") (pintype "passive"))
      (node (ref "C61") (pin "1") (pinfunction "1_1") (pintype "passive"))
      (node (ref "C62") (pin "1") (pinfunction "1_1") (pintype "passive"))
      (node (ref "C63") (pin "1") (pinfunction "1_1") (pintype "passive"))
      (node (ref "C70") (pin "1") (pinfunction "1_1") (pintype "passive"))
      (node (ref "C71") (pin "2") (pinfunction "2_2") (pintype "passive"))
      (node (ref "C76") (pin "1") (pinfunction "1_1") (pintype "passive"))
      (node (ref "C77") (pin "2") (pinfunction "2_2") (pintype "passive"))
      (node (ref "C78") (pin "1") (pinfunction "1_1") (pintype "passive"))
      (node (ref "C79") (pin "1") (pinfunction "1_1") (pintype "passive"))
      (node (ref "C80") (pin "1") (pinfunction "1_1") (pintype "passive"))
      (node (ref "C81") (pin "1") (pinfunction "1_1") (pintype "passive"))
      (node (ref "C82") (pin "1") (pinfunction "1_1") (pintype "passive"))
      (node (ref "C83") (pin "1") (pinfunction "1_1") (pintype "passive"))
      (node (ref "Q1") (pin "2") (pinfunction "S_2") (pintype "passive"))
      (node (ref "Q2") (pin "2") (pinfunction "S_2") (pintype "passive"))
      (node (ref "Q3") (pin "2") (pinfunction "S_2") (pintype "passive"))
      (node (ref "R17") (pin "1") (pinfunction "1_1") (pintype "passive"))
      (node (ref "R18") (pin "2") (pinfunction "2_2") (pintype "passive"))
      (node (ref "R22") (pin "1") (pinfunction "1_1") (pintype "passive"))
      (node (ref "R23") (pin "1") (pinfunction "1_1") (pintype "passive"))
      (node (ref "R31") (pin "1") (pinfunction "1_1") (pintype "passive"))
      (node (ref "R32") (pin "2") (pinfunction "2_2") (pintype "passive"))
      (node (ref "R36") (pin "1") (pinfunction "1_1") (pintype "passive"))
      (node (ref "R37") (pin "1") (pinfunction "1_1") (pintype "passive"))
      (node (ref "RF1") (pin "2") (pinfunction "2_2") (pintype "passive"))
      (node (ref "RF1") (pin "3") (pinfunction "3_3") (pintype "passive"))
      (node (ref "RF1") (pin "4") (pinfunction "4_4") (pintype "passive"))
      (node (ref "RF2") (pin "2") (pinfunction "2_2") (pintype "passive"))
      (node (ref "RF2") (pin "3") (pinfunction "3_3") (pintype "passive"))
      (node (ref "RF2") (pin "4") (pinfunction "4_4") (pintype "passive"))
      (node (ref "U12") (pin "4") (pinfunction "COMM_4") (pintype "passive"))
      (node (ref "U14") (pin "17") (pinfunction "EP_17") (pintype "passive"))
      (node (ref "U29") (pin "1") (pinfunction "1_1") (pintype "passive"))
      (node (ref "U7") (pin "4") (pinfunction "COMM_4") (pintype "passive"))
      (node (ref "U9") (pin "17") (pinfunction "EP_17") (pintype "passive"))
    )
    (net (code "38") (name "AVDD") (class "Default")
      (node (ref "C64") (pin "1") (pinfunction "1_1") (pintype "passive"))
      (node (ref "C65") (pin "1") (pinfunction "1_1") (pintype "passive"))
      (node (ref "C66") (pin "1") (pinfunction "1_1") (pintype "passive"))
      (node (ref "U10") (pin "13") (pinfunction "VD_13") (pintype "passive"))
      (node (ref "U10") (pin "30") (pinfunction "VD_30") (pintype "passive"))
      (node (ref "U10") (pin "31") (pinfunction "VD_31") (pintype "passive"))
      (node (ref "U10") (pin "48") (pinfunction "VD_48") (pintype "passive"))
    )
    (net (code "39") (name "DVDD") (class "Default")
      (node (ref "C72") (pin "2") (pinfunction "2_2") (pintype "passive"))
      (node (ref "C73") (pin "2") (pinfunction "2_2") (pintype "passive"))
      (node (ref "C74") (pin "2") (pinfunction "2_2") (pintype "passive"))
      (node (ref "C75") (pin "2") (pinfunction "2_2") (pintype "passive"))
      (node (ref "U10") (pin "15") (pinfunction "VDD_15") (pintype "passive"))
      (node (ref "U10") (pin "28") (pinfunction "VDD_28") (pintype "passive"))
      (node (ref "U10") (pin "33") (pinfunction "VDD_33") (pintype "passive"))
      (node (ref "U10") (pin "4") (pinfunction "DFS_4") (pintype "passive"))
      (node (ref "U10") (pin "46") (pinfunction "VDD_46") (pintype "passive"))
      (node (ref "U10") (pin "8") (pinfunction "S1_8") (pintype "passive"))
    )
    (net (code "40") (name "GND") (class "Default")
      (node (ref "C46") (pin "1") (pinfunction "1_1") (pintype "passive"))
      (node (ref "C48") (pin "1") (pinfunction "1_1") (pintype "passive"))
      (node (ref "C64") (pin "2") (pinfunction "2_2") (pintype "passive"))
      (node (ref "C65") (pin "2") (pinfunction "2_2") (pintype "passive"))
      (node (ref "C66") (pin "2") (pinfunction "2_2") (pintype "passive"))
      (node (ref "C72") (pin "1") (pinfunction "1_1") (pintype "passive"))
      (node (ref "C73") (pin "1") (pinfunction "1_1") (pintype "passive"))
      (node (ref "C74") (pin "1") (pinfunction "1_1") (pintype "passive"))
      (node (ref "C75") (pin "1") (pinfunction "1_1") (pintype "passive"))
      (node (ref "U10") (pin "1") (pinfunction "GND_1") (pintype "passive"))
      (node (ref "U10") (pin "12") (pinfunction "GND_12") (pintype "passive"))
      (node (ref "U10") (pin "16") (pinfunction "GND_16") (pintype "passive"))
      (node (ref "U10") (pin "27") (pinfunction "GND_27") (pintype "passive"))
      (node (ref "U10") (pin "29") (pinfunction "GND_29") (pintype "passive"))
      (node (ref "U10") (pin "32") (pinfunction "GND_32") (pintype "passive"))
      (node (ref "U10") (pin "34") (pinfunction "GND_34") (pintype "passive"))
      (node (ref "U10") (pin "45") (pinfunction "GND_45") (pintype "passive"))
      (node (ref "U10") (pin "9") (pinfunction "S2_9") (pintype "passive"))
    )
    (net (code "41") (name "Net-(C37-Pad1)") (class "Default")
      (node (ref "C37") (pin "1") (pinfunction "1_1") (pintype "passive"))
      (node (ref "C38") (pin "1") (pinfunction "1_1") (pintype "passive"))
      (node (ref "C43") (pin "2") (pinfunction "2_2") (pintype "passive"))
      (node (ref "K1") (pin "2") (pinfunction "2_2") (pintype "passive"))
      (node (ref "R12") (pin "1") (pinfunction "1_1") (pintype "passive"))
      (node (ref "R17") (pin "2") (pinfunction "2_2") (pintype "passive"))
    )
    (net (code "42") (name "Net-(C37-Pad2)") (class "Default")
      (node (ref "C37") (pin "2") (pinfunction "2_2") (pintype "passive"))
      (node (ref "C38") (pin "2") (pinfunction "2_2") (pintype "passive"))
      (node (ref "K1") (pin "7") (pinfunction "7_7") (pintype "passive"))
      (node (ref "R12") (pin "2") (pinfunction "2_2") (pintype "passive"))
    )
    (net (code "43") (name "Net-(C39-Pad1)") (class "Default")
      (node (ref "C39") (pin "1") (pinfunction "1_1") (pintype "passive"))
      (node (ref "K1") (pin "5") (pinfunction "5_5") (pintype "passive"))
      (node (ref "R13") (pin "1") (pinfunction "1_1") (pintype "passive"))
    )
    (net (code "44") (name "Net-(C39-Pad2)") (class "Default")
      (node (ref "C39") (pin "2") (pinfunction "2_2") (pintype "passive"))
      (node (ref "C44") (pin "1") (pinfunction "1_1") (pintype "passive"))
      (node (ref "C45") (pin "2") (pinfunction "2_2") (pintype "passive"))
      (node (ref "K1") (pin "4") (pinfunction "4_4") (pintype "passive"))
      (node (ref "R13") (pin "2") (pinfunction "2_2") (pintype "passive"))
      (node (ref "R18") (pin "1") (pinfunction "1_1") (pintype "passive"))
    )
    (net (code "45") (name "Net-(C67-Pad1)") (class "Default")
      (node (ref "C67") (pin "1") (pinfunction "1_1") (pintype "passive"))
      (node (ref "C68") (pin "1") (pinfunction "1_1") (pintype "passive"))
      (node (ref "C76") (pin "2") (pinfunction "2_2") (pintype "passive"))
      (node (ref "K3") (pin "2") (pinfunction "2_2") (pintype "passive"))
      (node (ref "R27") (pin "1") (pinfunction "1_1") (pintype "passive"))
      (node (ref "R31") (pin "2") (pinfunction "2_2") (pintype "passive"))
    )
    (net (code "46") (name "Net-(C67-Pad2)") (class "Default")
      (node (ref "C67") (pin "2") (pinfunction "2_2") (pintype "passive"))
      (node (ref "C68") (pin "2") (pinfunction "2_2") (pintype "passive"))
      (node (ref "K3") (pin "7") (pinfunction "7_7") (pintype "passive"))
      (node (ref "R27") (pin "2") (pinfunction "2_2") (pintype "passive"))
    )
    (net (code "47") (name "Net-(C69-Pad1)") (class "Default")
      (node (ref "C69") (pin "1") (pinfunction "1_1") (pintype "passive"))
      (node (ref "K3") (pin "5") (pinfunction "5_5") (pintype "passive"))
      (node (ref "R28") (pin "1") (pinfunction "1_1") (pintype "passive"))
    )
    (net (code "48") (name "Net-(C69-Pad2)") (class "Default")
      (node (ref "C69") (pin "2") (pinfunction "2_2") (pintype "passive"))
      (node (ref "C77") (pin "1") (pinfunction "1_1") (pintype "passive"))
      (node (ref "C78") (pin "2") (pinfunction "2_2") (pintype "passive"))
      (node (ref "K3") (pin "4") (pinfunction "4_4") (pintype "passive"))
      (node (ref "R28") (pin "2") (pinfunction "2_2") (pintype "passive"))
      (node (ref "R32") (pin "1") (pinfunction "1_1") (pintype "passive"))
    )
    (net (code "49") (name "Net-(Q1-G)") (class "Default")
      (node (ref "Q1") (pin "1") (pinfunction "G_1") (pintype "passive"))
      (node (ref "R11") (pin "1") (pinfunction "1_1") (pintype "passive"))
    )
    (net (code "50") (name "Net-(Q2-G)") (class "Default")
      (node (ref "Q2") (pin "1") (pinfunction "G_1") (pintype "passive"))
      (node (ref "R35") (pin "1") (pinfunction "1_1") (pintype "passive"))
    )
    (net (code "51") (name "Net-(Q3-G)") (class "Default")
      (node (ref "Q3") (pin "1") (pinfunction "G_1") (pintype "passive"))
      (node (ref "R39") (pin "1") (pinfunction "1_1") (pintype "passive"))
    )
    (net (code "52") (name "Net-(RF1-OUT)") (class "Default")
      (node (ref "C27") (pin "1") (pinfunction "1_1") (pintype "passive"))
      (node (ref "C36") (pin "1") (pinfunction "1_1") (pintype "passive"))
      (node (ref "RF1") (pin "1") (pinfunction "OUT_1") (pintype "passive"))
      (node (ref "TP1") (pin "1") (pinfunction "1_1") (pintype "passive"))
      (node (ref "U8") (pin "4") (pinfunction "INOUT1_4") (pintype "passive"))
    )
    (net (code "53") (name "Net-(RF2-OUT)") (class "Default")
      (node (ref "C54") (pin "1") (pinfunction "1_1") (pintype "passive"))
      (node (ref "C59") (pin "1") (pinfunction "1_1") (pintype "passive"))
      (node (ref "RF2") (pin "1") (pinfunction "OUT_1") (pintype "passive"))
      (node (ref "TP2") (pin "1") (pinfunction "1_1") (pintype "passive"))
      (node (ref "U13") (pin "4") (pinfunction "INOUT1_4") (pintype "passive"))
    )
    (net (code "54") (name "Net-(U6-+IN)") (class "Default")
      (node (ref "K1") (pin "3") (pinfunction "3_3") (pintype "passive"))
      (node (ref "TP8") (pin "1") (pinfunction "1_1") (pintype "passive"))
      (node (ref "U6") (pin "3") (pinfunction "+IN_3") (pintype "passive"))
    )
    (net (code "55") (name "Net-(U6--IN)") (class "Default")
      (node (ref "K2") (pin "4") (pinfunction "4_4") (pintype "passive"))
      (node (ref "TP6") (pin "1") (pinfunction "1_1") (pintype "passive"))
      (node (ref "U6") (pin "1") (pinfunction "VOUT_1") (pintype "passive"))
      (node (ref "U6") (pin "4") (pinfunction "-IN_4") (pintype "passive"))
      (node (ref "U7") (pin "3") (pinfunction "VINP_3") (pintype "passive"))
    )
    (net (code "56") (name "Net-(U7-FDBK)") (class "Default")
      (node (ref "R14") (pin "1") (pinfunction "1_1") (pintype "passive"))
      (node (ref "TP9") (pin "1") (pinfunction "1_1") (pintype "passive"))
      (node (ref "U7") (pin "5") (pinfunction "FDBK_5") (pintype "passive"))
      (node (ref "U7") (pin "7") (pinfunction "VOUT_7") (pintype "passive"))
    )
    (net (code "57") (name "Net-(U8-CATH)") (class "Default")
      (node (ref "R22") (pin "2") (pinfunction "2_2") (pintype "passive"))
      (node (ref "U8") (pin "2") (pinfunction "CATH_2") (pintype "passive"))
    )
    (net (code "58") (name "Net-(U8-INOUT2)") (class "Default")
      (node (ref "C27") (pin "2") (pinfunction "2_2") (pintype "passive"))
      (node (ref "C36") (pin "2") (pinfunction "2_2") (pintype "passive"))
      (node (ref "K1") (pin "6") (pinfunction "6_6") (pintype "passive"))
      (node (ref "TP4") (pin "1") (pinfunction "1_1") (pintype "passive"))
      (node (ref "U8") (pin "3") (pinfunction "INOUT2_3") (pintype "passive"))
    )
    (net (code "59") (name "Net-(U9-+FB)") (class "Default")
      (node (ref "R20") (pin "2") (pinfunction "2_2") (pintype "passive"))
      (node (ref "U9") (pin "4") (pinfunction "+FB_4") (pintype "passive"))
    )
    (net (code "60") (name "Net-(U9-+IN)") (class "Default")
      (node (ref "R14") (pin "2") (pinfunction "2_2") (pintype "passive"))
      (node (ref "R15") (pin "1") (pinfunction "1_1") (pintype "passive"))
      (node (ref "U9") (pin "2") (pinfunction "+IN_2") (pintype "passive"))
    )
    (net (code "61") (name "Net-(U9-VOCM)") (class "Default")
      (node (ref "C52") (pin "2") (pinfunction "2_2") (pintype "passive"))
      (node (ref "R23") (pin "2") (pinfunction "2_2") (pintype "passive"))
      (node (ref "R24") (pin "2") (pinfunction "2_2") (pintype "passive"))
      (node (ref "U9") (pin "9") (pinfunction "VOCM_9") (pintype "passive"))
    )
    (net (code "62") (name "Net-(U9-–FB)") (class "Default")
      (node (ref "R15") (pin "2") (pinfunction "2_2") (pintype "passive"))
      (node (ref "U9") (pin "1") (pinfunction "–FB_1") (pintype "passive"))
    )
    (net (code "63") (name "Net-(U9-–IN)") (class "Default")
      (node (ref "R19") (pin "2") (pinfunction "2_2") (pintype "passive"))
      (node (ref "R20") (pin "1") (pinfunction "1_1") (pintype "passive"))
      (node (ref "U9") (pin "3") (pinfunction "–IN_3") (pintype "passive"))
    )
    (net (code "64") (name "Net-(U10-AINA#)") (class "Default")
      (node (ref "C42") (pin "1") (pinfunction "1_1") (pintype "passive"))
      (node (ref "R21") (pin "2") (pinfunction "2_2") (pintype "passive"))
      (node (ref "U10") (pin "3") (pinfunction "AINA#_3") (pintype "passive"))
      (node (ref "U30") (pin "1") (pinfunction "1_1") (pintype "passive"))
    )
    (net (code "65") (name "Net-(U10-AINA)") (class "Default")
      (node (ref "C42") (pin "2") (pinfunction "2_2") (pintype "passive"))
      (node (ref "R16") (pin "2") (pinfunction "2_2") (pintype "passive"))
      (node (ref "TP11") (pin "1") (pinfunction "1_1") (pintype "passive"))
      (node (ref "U10") (pin "2") (pinfunction "AINA_2") (pintype "passive"))
    )
    (net (code "66") (name "Net-(U10-AINB#)") (class "Default")
      (node (ref "C53") (pin "1") (pinfunction "1_1") (pintype "passive"))
      (node (ref "R26") (pin "2") (pinfunction "2_2") (pintype "passive"))
      (node (ref "U10") (pin "10") (pinfunction "AINB#_10") (pintype "passive"))
      (node (ref "U31") (pin "1") (pinfunction "1_1") (pintype "passive"))
    )
    (net (code "67") (name "Net-(U10-AINB)") (class "Default")
      (node (ref "C53") (pin "2") (pinfunction "2_2") (pintype "passive"))
      (node (ref "R25") (pin "2") (pinfunction "2_2") (pintype "passive"))
      (node (ref "TP12") (pin "1") (pinfunction "1_1") (pintype "passive"))
      (node (ref "U10") (pin "11") (pinfunction "AINB_11") (pintype "passive"))
    )
    (net (code "68") (name "Net-(U10-D0A)") (class "Default")
      (node (ref "RN1") (pin "1") (pinfunction "1_1") (pintype "passive"))
      (node (ref "U10") (pin "37") (pinfunction "D0A_37") (pintype "passive"))
    )
    (net (code "69") (name "Net-(U10-D0B)") (class "Default")
      (node (ref "RN3") (pin "1") (pinfunction "1_1") (pintype "passive"))
      (node (ref "U10") (pin "24") (pinfunction "D0B_24") (pintype "passive"))
    )
    (net (code "70") (name "Net-(U10-D1A)") (class "Default")
      (node (ref "RN1") (pin "2") (pinfunction "2_2") (pintype "passive"))
      (node (ref "U10") (pin "38") (pinfunction "D1A_38") (pintype "passive"))
    )
    (net (code "71") (name "Net-(U10-D1B)") (class "Default")
      (node (ref "RN3") (pin "2") (pinfunction "2_2") (pintype "passive"))
      (node (ref "U10") (pin "23") (pinfunction "D1B_23") (pintype "passive"))
    )
    (net (code "72") (name "Net-(U10-D2A)") (class "Default")
      (node (ref "RN1") (pin "3") (pinfunction "3_3") (pintype "passive"))
      (node (ref "U10") (pin "39") (pinfunction "D2A_39") (pintype "passive"))
    )
    (net (code "73") (name "Net-(U10-D2B)") (class "Default")
      (node (ref "RN3") (pin "3") (pinfunction "3_3") (pintype "passive"))
      (node (ref "U10") (pin "22") (pinfunction "D2B_22") (pintype "passive"))
    )
    (net (code "74") (name "Net-(U10-D3A)") (class "Default")
      (node (ref "RN1") (pin "4") (pinfunction "4_4") (pintype "passive"))
      (node (ref "U10") (pin "40") (pinfunction "D3A_40") (pintype "passive"))
    )
    (net (code "75") (name "Net-(U10-D3B)") (class "Default")
      (node (ref "RN3") (pin "4") (pinfunction "4_4") (pintype "passive"))
      (node (ref "U10") (pin "21") (pinfunction "D3B_21") (pintype "passive"))
    )
    (net (code "76") (name "Net-(U10-D4A)") (class "Default")
      (node (ref "RN2") (pin "1") (pinfunction "1_1") (pintype "passive"))
      (node (ref "U10") (pin "41") (pinfunction "D4A_41") (pintype "passive"))
    )
    (net (code "77") (name "Net-(U10-D4B)") (class "Default")
      (node (ref "RN4") (pin "1") (pinfunction "1_1") (pintype "passive"))
      (node (ref "U10") (pin "20") (pinfunction "D4B_20") (pintype "passive"))
    )
    (net (code "78") (name "Net-(U10-D5A)") (class "Default")
      (node (ref "RN2") (pin "2") (pinfunction "2_2") (pintype "passive"))
      (node (ref "U10") (pin "42") (pinfunction "D5A_42") (pintype "passive"))
    )
    (net (code "79") (name "Net-(U10-D5B)") (class "Default")
      (node (ref "RN4") (pin "2") (pinfunction "2_2") (pintype "passive"))
      (node (ref "U10") (pin "19") (pinfunction "D5B_19") (pintype "passive"))
    )
    (net (code "80") (name "Net-(U10-D6A)") (class "Default")
      (node (ref "RN2") (pin "3") (pinfunction "3_3") (pintype "passive"))
      (node (ref "U10") (pin "43") (pinfunction "D6A_43") (pintype "passive"))
    )
    (net (code "81") (name "Net-(U10-D6B)") (class "Default")
      (node (ref "RN4") (pin "3") (pinfunction "3_3") (pintype "passive"))
      (node (ref "U10") (pin "18") (pinfunction "D6B_18") (pintype "passive"))
    )
    (net (code "82") (name "Net-(U10-D7A_(MSB))") (class "Default")
      (node (ref "RN2") (pin "4") (pinfunction "4_4") (pintype "passive"))
      (node (ref "U10") (pin "44") (pinfunction "D7A_(MSB)_44") (pintype "passive"))
    )
    (net (code "83") (name "Net-(U10-D7B_(MSB))") (class "Default")
      (node (ref "RN4") (pin "4") (pinfunction "4_4") (pintype "passive"))
      (node (ref "U10") (pin "17") (pinfunction "D7B_(MSB)_17") (pintype "passive"))
    )
    (net (code "84") (name "Net-(U10-ENCA)") (class "Default")
      (node (ref "R71") (pin "1") (pinfunction "1_1") (pintype "passive"))
      (node (ref "U10") (pin "47") (pinfunction "ENCA_47") (pintype "passive"))
    )
    (net (code "85") (name "Net-(U10-ENCB)") (class "Default")
      (node (ref "R72") (pin "1") (pinfunction "1_1") (pintype "passive"))
      (node (ref "U10") (pin "14") (pinfunction "ENCB_14") (pintype "passive"))
    )
    (net (code "86") (name "Net-(U11-+IN)") (class "Default")
      (node (ref "K3") (pin "3") (pinfunction "3_3") (pintype "passive"))
      (node (ref "TP7") (pin "1") (pinfunction "1_1") (pintype "passive"))
      (node (ref "U11") (pin "3") (pinfunction "+IN_3") (pintype "passive"))
    )
    (net (code "87") (name "Net-(U11--IN)") (class "Default")
      (node (ref "K2") (pin "2") (pinfunction "2_2") (pintype "passive"))
      (node (ref "R76") (pin "1") (pinfunction "1_1") (pintype "passive"))
      (node (ref "U11") (pin "1") (pinfunction "VOUT_1") (pintype "passive"))
      (node (ref "U11") (pin "4") (pinfunction "-IN_4") (pintype "passive"))
    )
    (net (code "88") (name "Net-(U12-FDBK)") (class "Default")
      (node (ref "R29") (pin "1") (pinfunction "1_1") (pintype "passive"))
      (node (ref "TP10") (pin "1") (pinfunction "1_1") (pintype "passive"))
      (node (ref "U12") (pin "5") (pinfunction "FDBK_5") (pintype "passive"))
      (node (ref "U12") (pin "7") (pinfunction "VOUT_7") (pintype "passive"))
    )
    (net (code "89") (name "Net-(U12-VINP)") (class "Default")
      (node (ref "K2") (pin "3") (pinfunction "3_3") (pintype "passive"))
      (node (ref "R76") (pin "2") (pinfunction "2_2") (pintype "passive"))
      (node (ref "U12") (pin "3") (pinfunction "VINP_3") (pintype "passive"))
    )
    (net (code "90") (name "Net-(U13-CATH)") (class "Default")
      (node (ref "R36") (pin "2") (pinfunction "2_2") (pintype "passive"))
      (node (ref "U13") (pin "2") (pinfunction "CATH_2") (pintype "passive"))
    )
    (net (code "91") (name "Net-(U13-INOUT2)") (class "Default")
      (node (ref "C54") (pin "2") (pinfunction "2_2") (pintype "passive"))
      (node (ref "C59") (pin "2") (pinfunction "2_2") (pintype "passive"))
      (node (ref "K3") (pin "6") (pinfunction "6_6") (pintype "passive"))
      (node (ref "TP3") (pin "1") (pinfunction "1_1") (pintype "passive"))
      (node (ref "U13") (pin "3") (pinfunction "INOUT2_3") (pintype "passive"))
    )
    (net (code "92") (name "Net-(U14-+FB)") (class "Default")
      (node (ref "R34") (pin "2") (pinfunction "2_2") (pintype "passive"))
      (node (ref "U14") (pin "4") (pinfunction "+FB_4") (pintype "passive"))
    )
    (net (code "93") (name "Net-(U14-+IN)") (class "Default")
      (node (ref "R29") (pin "2") (pinfunction "2_2") (pintype "passive"))
      (node (ref "R30") (pin "1") (pinfunction "1_1") (pintype "passive"))
      (node (ref "U14") (pin "2") (pinfunction "+IN_2") (pintype "passive"))
    )
    (net (code "94") (name "Net-(U14-VOCM)") (class "Default")
      (node (ref "C83") (pin "2") (pinfunction "2_2") (pintype "passive"))
      (node (ref "R37") (pin "2") (pinfunction "2_2") (pintype "passive"))
      (node (ref "R38") (pin "2") (pinfunction "2_2") (pintype "passive"))
      (node (ref "U14") (pin "9") (pinfunction "VOCM_9") (pintype "passive"))
    )
    (net (code "95") (name "Net-(U14-–FB)") (class "Default")
      (node (ref "R30") (pin "2") (pinfunction "2_2") (pintype "passive"))
      (node (ref "U14") (pin "1") (pinfunction "–FB_1") (pintype "passive"))
    )
    (net (code "96") (name "Net-(U14-–IN)") (class "Default")
      (node (ref "R33") (pin "2") (pinfunction "2_2") (pintype "passive"))
      (node (ref "R34") (pin "1") (pinfunction "1_1") (pintype "passive"))
      (node (ref "U14") (pin "3") (pinfunction "–IN_3") (pintype "passive"))
    )
    (net (code "97") (name "VCC_4V5") (class "Default")
      (node (ref "C28") (pin "2") (pinfunction "2_2") (pintype "passive"))
      (node (ref "C29") (pin "2") (pinfunction "2_2") (pintype "passive"))
      (node (ref "C32") (pin "2") (pinfunction "2_2") (pintype "passive"))
      (node (ref "C33") (pin "2") (pinfunction "2_2") (pintype "passive"))
      (node (ref "C34") (pin "2") (pinfunction "2_2") (pintype "passive"))
      (node (ref "C35") (pin "2") (pinfunction "2_2") (pintype "passive"))
      (node (ref "C55") (pin "2") (pinfunction "2_2") (pintype "passive"))
      (node (ref "C56") (pin "2") (pinfunction "2_2") (pintype "passive"))
      (node (ref "C57") (pin "2") (pinfunction "2_2") (pintype "passive"))
      (node (ref "C58") (pin "2") (pinfunction "2_2") (pintype "passive"))
      (node (ref "C60") (pin "2") (pinfunction "2_2") (pintype "passive"))
      (node (ref "C61") (pin "2") (pinfunction "2_2") (pintype "passive"))
      (node (ref "U11") (pin "5") (pinfunction "+VS_5") (pintype "passive"))
      (node (ref "U12") (pin "8") (pinfunction "VPOS_8") (pintype "passive"))
      (node (ref "U14") (pin "12") (pinfunction "PD#_12") (pintype "passive"))
      (node (ref "U14") (pin "5") (pinfunction "+VS_5") (pintype "passive"))
      (node (ref "U14") (pin "6") (pinfunction "+VS_6") (pintype "passive"))
      (node (ref "U14") (pin "7") (pinfunction "+VS_7") (pintype "passive"))
      (node (ref "U14") (pin "8") (pinfunction "+VS_8") (pintype "passive"))
      (node (ref "U6") (pin "5") (pinfunction "+VS_5") (pintype "passive"))
      (node (ref "U7") (pin "8") (pinfunction "VPOS_8") (pintype "passive"))
      (node (ref "U9") (pin "12") (pinfunction "PD#_12") (pintype "passive"))
      (node (ref "U9") (pin "5") (pinfunction "+VS_5") (pintype "passive"))
      (node (ref "U9") (pin "6") (pinfunction "+VS_6") (pintype "passive"))
      (node (ref "U9") (pin "7") (pinfunction "+VS_7") (pintype "passive"))
      (node (ref "U9") (pin "8") (pinfunction "+VS_8") (pintype "passive"))
    )
    (net (code "98") (name "VDD_5V0") (class "Default")
      (node (ref "K1") (pin "1") (pinfunction "1_1") (pintype "passive"))
      (node (ref "K2") (pin "1") (pinfunction "1_1") (pintype "passive"))
      (node (ref "K3") (pin "1") (pinfunction "1_1") (pintype "passive"))
    )
    (net (code "99") (name "VEE_5V0") (class "Default")
      (node (ref "C30") (pin "2") (pinfunction "2_2") (pintype "passive"))
      (node (ref "C31") (pin "2") (pinfunction "2_2") (pintype "passive"))
      (node (ref "C47") (pin "2") (pinfunction "2_2") (pintype "passive"))
      (node (ref "C49") (pin "2") (pinfunction "2_2") (pintype "passive"))
      (node (ref "C50") (pin "2") (pinfunction "2_2") (pintype "passive"))
      (node (ref "C51") (pin "2") (pinfunction "2_2") (pintype "passive"))
      (node (ref "C62") (pin "2") (pinfunction "2_2") (pintype "passive"))
      (node (ref "C63") (pin "2") (pinfunction "2_2") (pintype "passive"))
      (node (ref "C79") (pin "2") (pinfunction "2_2") (pintype "passive"))
      (node (ref "C80") (pin "2") (pinfunction "2_2") (pintype "passive"))
      (node (ref "C81") (pin "2") (pinfunction "2_2") (pintype "passive"))
      (node (ref "C82") (pin "2") (pinfunction "2_2") (pintype "passive"))
      (node (ref "U11") (pin "2") (pinfunction "-VS_2") (pintype "passive"))
      (node (ref "U12") (pin "6") (pinfunction "VNEG_6") (pintype "passive"))
      (node (ref "U14") (pin "13") (pinfunction "–VS_13") (pintype "passive"))
      (node (ref "U14") (pin "14") (pinfunction "–VS_14") (pintype "passive"))
      (node (ref "U14") (pin "15") (pinfunction "–VS_15") (pintype "passive"))
      (node (ref "U14") (pin "16") (pinfunction "–VS_16") (pintype "passive"))
      (node (ref "U6") (pin "2") (pinfunction "-VS_2") (pintype "passive"))
      (node (ref "U7") (pin "6") (pinfunction "VNEG_6") (pintype "passive"))
      (node (ref "U9") (pin "13") (pinfunction "–VS_13") (pintype "passive"))
      (node (ref "U9") (pin "14") (pinfunction "–VS_14") (pintype "passive"))
      (node (ref "U9") (pin "15") (pinfunction "–VS_15") (pintype "passive"))
      (node (ref "U9") (pin "16") (pinfunction "–VS_16") (pintype "passive"))
    )
    (net (code "100") (name "unconnected-(K2-Pad5)") (class "Default")
      (node (ref "K2") (pin "5") (pinfunction "5_5") (pintype "passive+no_connect"))
    )
    (net (code "101") (name "unconnected-(K2-Pad6)") (class "Default")
      (node (ref "K2") (pin "6") (pinfunction "6_6") (pintype "passive+no_connect"))
    )
    (net (code "102") (name "unconnected-(K2-Pad7)") (class "Default")
      (node (ref "K2") (pin "7") (pinfunction "7_7") (pintype "passive+no_connect"))
    )
    (net (code "103") (name "unconnected-(U10-NC-Pad25)") (class "Default")
      (node (ref "U10") (pin "25") (pinfunction "NC_25") (pintype "passive+no_connect"))
    )
    (net (code "104") (name "unconnected-(U10-NC-Pad26)") (class "Default")
      (node (ref "U10") (pin "26") (pinfunction "NC_26") (pintype "passive+no_connect"))
    )
    (net (code "105") (name "unconnected-(U10-NC-Pad35)") (class "Default")
      (node (ref "U10") (pin "35") (pinfunction "NC_35") (pintype "passive+no_connect"))
    )
    (net (code "106") (name "unconnected-(U10-NC-Pad36)") (class "Default")
      (node (ref "U10") (pin "36") (pinfunction "NC_36") (pintype "passive+no_connect"))
    )
  )
)
